# tm7_revF.net
KiCad netlist of a schematic drawn in EAGLE
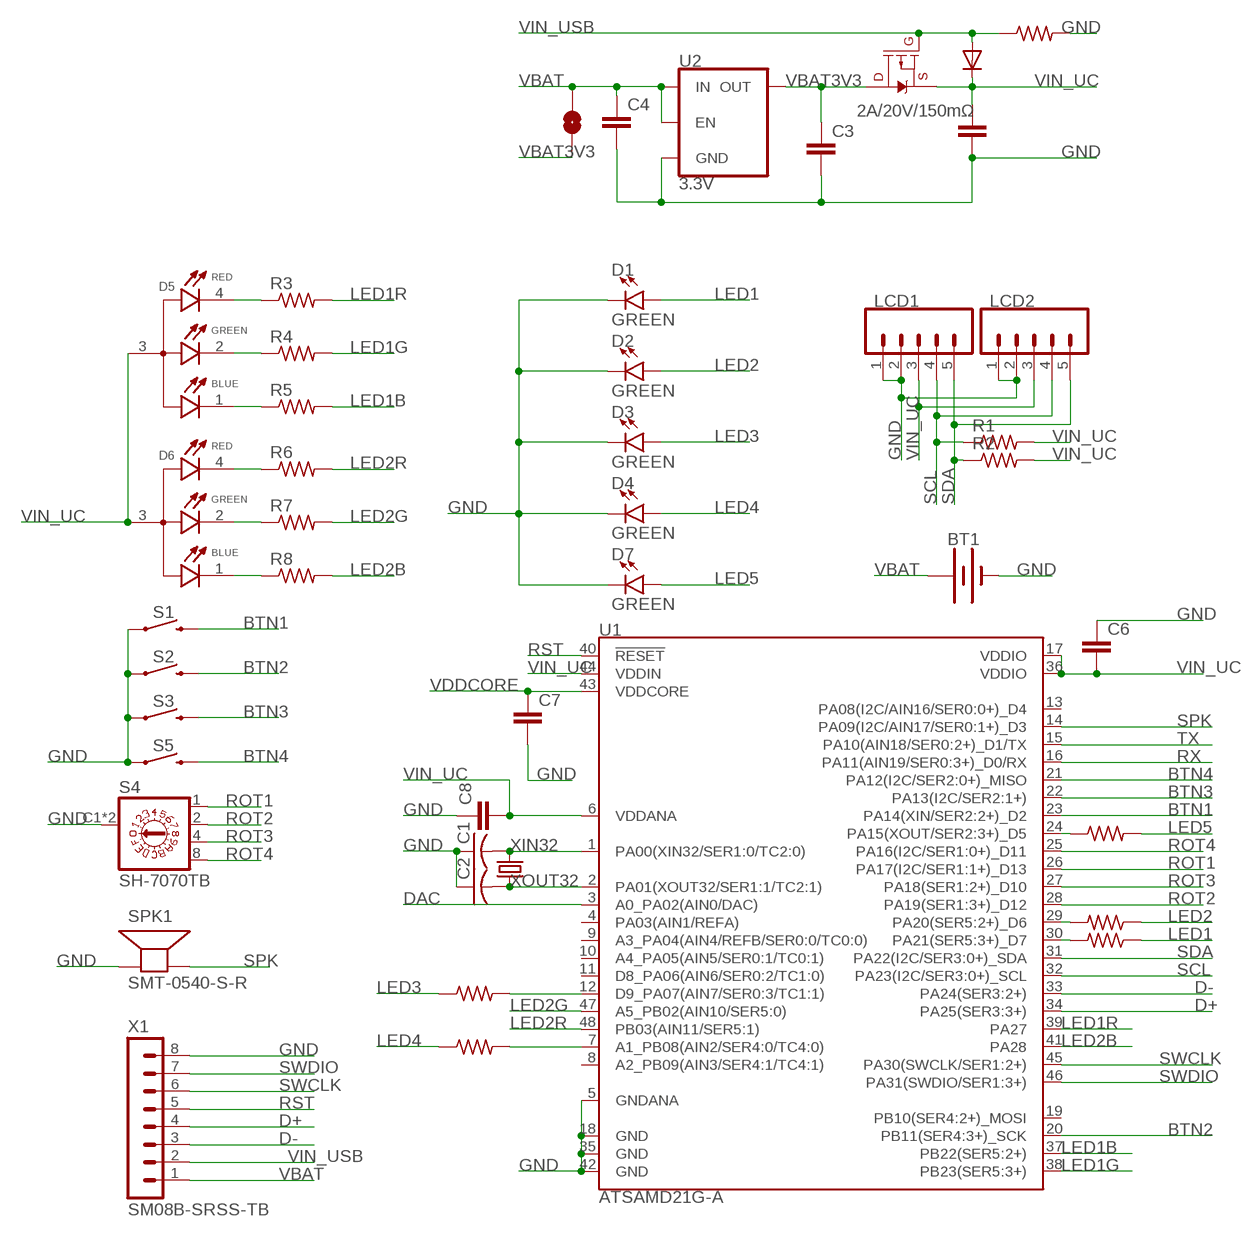
[diagram p0: schematic, sheet 1]

(export (version "E")
  (design (tool "Eeschema 10.0.6"))
  (components
    (comp (ref "BT1")
      (value "BATTERY-20MM_SMD_4LEGS_OVERPASTE_INNER")
      (footprint "eagle-import:BATTCON_20MM_4LEGS_OVERPASTE_INNER")
      (libsource (lib "eagle-import") (part "BATTERY-20MM_SMD_4LEGS_OVERPASTE_INNER"))
    )
    (comp (ref "C1")
      (value "C-USC0603")
      (footprint "eagle-import:C0603")
      (libsource (lib "eagle-import") (part "C-USC0603"))
    )
    (comp (ref "C2")
      (value "C-USC0603")
      (footprint "eagle-import:C0603")
      (libsource (lib "eagle-import") (part "C-USC0603"))
    )
    (comp (ref "C3")
      (value "C-EUC0603")
      (footprint "eagle-import:C0603")
      (libsource (lib "eagle-import") (part "C-EUC0603"))
    )
    (comp (ref "C4")
      (value "C-EUC0603")
      (footprint "eagle-import:C0603")
      (libsource (lib "eagle-import") (part "C-EUC0603"))
    )
    (comp (ref "C6")
      (value "C-EUC0603")
      (footprint "eagle-import:C0603")
      (libsource (lib "eagle-import") (part "C-EUC0603"))
    )
    (comp (ref "C7")
      (value "C-EUC0603")
      (footprint "eagle-import:C0603")
      (libsource (lib "eagle-import") (part "C-EUC0603"))
    )
    (comp (ref "C8")
      (value "C-EUC0603")
      (footprint "eagle-import:C0603")
      (libsource (lib "eagle-import") (part "C-EUC0603"))
    )
    (comp (ref "C9")
      (value "C-EUC0603")
      (footprint "eagle-import:C0603")
      (libsource (lib "eagle-import") (part "C-EUC0603"))
    )
    (comp (ref "D1")
      (value "GREEN")
      (footprint "eagle-import:LED-1206")
      (libsource (lib "eagle-import") (part "LED-GREEN1206"))
    )
    (comp (ref "D2")
      (value "GREEN")
      (footprint "eagle-import:LED-1206")
      (libsource (lib "eagle-import") (part "LED-GREEN1206"))
    )
    (comp (ref "D3")
      (value "GREEN")
      (footprint "eagle-import:LED-1206")
      (libsource (lib "eagle-import") (part "LED-GREEN1206"))
    )
    (comp (ref "D4")
      (value "GREEN")
      (footprint "eagle-import:LED-1206")
      (libsource (lib "eagle-import") (part "LED-GREEN1206"))
    )
    (comp (ref "D5")
      (value "EAST1616RGBA3")
      (footprint "eagle-import:LED_EAST1616RGBA3")
      (fields (field (name "MF") "Everlight Electronics"))
      (libsource (lib "eagle-import") (part "EAST1616RGBA3"))
    )
    (comp (ref "D6")
      (value "EAST1616RGBA3")
      (footprint "eagle-import:LED_EAST1616RGBA3")
      (fields (field (name "MF") "Everlight Electronics"))
      (libsource (lib "eagle-import") (part "EAST1616RGBA3"))
    )
    (comp (ref "D7")
      (value "GREEN")
      (footprint "eagle-import:LED-1206")
      (libsource (lib "eagle-import") (part "LED-GREEN1206"))
    )
    (comp (ref "D8")
      (value "DIODESOD-323F")
      (footprint "eagle-import:SOD-323F")
      (libsource (lib "eagle-import") (part "DIODESOD-323F"))
    )
    (comp (ref "JP1")
      (value "JUMPER-SMT_2_NO_NO-SILK")
      (footprint "eagle-import:SMT-JUMPER_2_NO_NO-SILK")
      (libsource (lib "eagle-import") (part "JUMPER-SMT_2_NO_NO-SILK"))
    )
    (comp (ref "LCD1")
      (value "CONN_05VERT_FEMALE_HEADER")
      (footprint "eagle-import:1X05_SMD_VERTICAL_COMBO")
      (libsource (lib "eagle-import") (part "CONN_05VERT_FEMALE_HEADER"))
    )
    (comp (ref "LCD2")
      (value "CONN_05VERT_FEMALE_HEADER")
      (footprint "eagle-import:1X05_SMD_VERTICAL_COMBO")
      (libsource (lib "eagle-import") (part "CONN_05VERT_FEMALE_HEADER"))
    )
    (comp (ref "Q1")
      (value "2A/20V/150mΩ")
      (footprint "eagle-import:SOT26")
      (libsource (lib "eagle-import") (part "MOSFET_PCH_DUAL-DMP2240UDM"))
    )
    (comp (ref "R1")
      (value "R-US_R0603")
      (footprint "eagle-import:R0603")
      (libsource (lib "eagle-import") (part "rcl_334_R-US_R0603"))
    )
    (comp (ref "R2")
      (value "R-US_R0603")
      (footprint "eagle-import:R0603")
      (libsource (lib "eagle-import") (part "rcl_334_R-US_R0603"))
    )
    (comp (ref "R3")
      (value "R-US_R0603")
      (footprint "eagle-import:R0603")
      (libsource (lib "eagle-import") (part "rcl_334_R-US_R0603"))
    )
    (comp (ref "R4")
      (value "R-US_R0603")
      (footprint "eagle-import:R0603")
      (libsource (lib "eagle-import") (part "rcl_334_R-US_R0603"))
    )
    (comp (ref "R5")
      (value "R-US_R0603")
      (footprint "eagle-import:R0603")
      (libsource (lib "eagle-import") (part "rcl_334_R-US_R0603"))
    )
    (comp (ref "R6")
      (value "R-US_R0603")
      (footprint "eagle-import:R0603")
      (libsource (lib "eagle-import") (part "rcl_334_R-US_R0603"))
    )
    (comp (ref "R7")
      (value "R-US_R0603")
      (footprint "eagle-import:R0603")
      (libsource (lib "eagle-import") (part "rcl_334_R-US_R0603"))
    )
    (comp (ref "R8")
      (value "R-US_R0603")
      (footprint "eagle-import:R0603")
      (libsource (lib "eagle-import") (part "rcl_334_R-US_R0603"))
    )
    (comp (ref "R9")
      (value "R-US_R0603")
      (footprint "eagle-import:R0603")
      (libsource (lib "eagle-import") (part "rcl_334_R-US_R0603"))
    )
    (comp (ref "R10")
      (value "R-US_R0603")
      (footprint "eagle-import:R0603")
      (libsource (lib "eagle-import") (part "rcl_334_R-US_R0603"))
    )
    (comp (ref "R11")
      (value "R-US_R0603")
      (footprint "eagle-import:R0603")
      (libsource (lib "eagle-import") (part "rcl_334_R-US_R0603"))
    )
    (comp (ref "R12")
      (value "R-US_R0603")
      (footprint "eagle-import:R0603")
      (libsource (lib "eagle-import") (part "rcl_334_R-US_R0603"))
    )
    (comp (ref "R13")
      (value "R-US_R0603")
      (footprint "eagle-import:R0603")
      (libsource (lib "eagle-import") (part "rcl_334_R-US_R0603"))
    )
    (comp (ref "R14")
      (value "R-US_R0603")
      (footprint "eagle-import:R0603")
      (libsource (lib "eagle-import") (part "R-US_R0603"))
    )
    (comp (ref "S1")
      (value "MOMENTARY-SWITCH-SPST-SMD-6.0X3.5MM")
      (footprint "eagle-import:TACTILE_SWITCH_SMD_6.0X3.5MM")
      (libsource (lib "eagle-import") (part "MOMENTARY-SWITCH-SPST-SMD-6.0X3.5MM"))
    )
    (comp (ref "S2")
      (value "MOMENTARY-SWITCH-SPST-SMD-6.0X3.5MM")
      (footprint "eagle-import:TACTILE_SWITCH_SMD_6.0X3.5MM")
      (libsource (lib "eagle-import") (part "MOMENTARY-SWITCH-SPST-SMD-6.0X3.5MM"))
    )
    (comp (ref "S3")
      (value "MOMENTARY-SWITCH-SPST-SMD-6.0X3.5MM")
      (footprint "eagle-import:TACTILE_SWITCH_SMD_6.0X3.5MM")
      (libsource (lib "eagle-import") (part "MOMENTARY-SWITCH-SPST-SMD-6.0X3.5MM"))
    )
    (comp (ref "S4")
      (value "SH-7070TB")
      (footprint "eagle-import:SH-7070B")
      (fields (field (name "MF") "Nidec Copal"))
      (libsource (lib "eagle-import") (part "SH-7070TB"))
    )
    (comp (ref "S5")
      (value "MOMENTARY-SWITCH-SPST-SMD-6.0X3.5MM")
      (footprint "eagle-import:TACTILE_SWITCH_SMD_6.0X3.5MM")
      (libsource (lib "eagle-import") (part "MOMENTARY-SWITCH-SPST-SMD-6.0X3.5MM"))
    )
    (comp (ref "SPK1")
      (value "SMT-0540-S-R")
      (footprint "eagle-import:SMT-0540-S-R")
      (fields (field (name "MF") "PUI"))
      (libsource (lib "eagle-import") (part "SMT-0540-S-R"))
    )
    (comp (ref "U1")
      (value "ATSAMD21G-A")
      (footprint "eagle-import:TQFP-48")
      (libsource (lib "eagle-import") (part "ATSAMD21G-A"))
    )
    (comp (ref "U2")
      (value "3.3V")
      (footprint "eagle-import:SOT23-5")
      (libsource (lib "eagle-import") (part "V_REG_AP2112K-3.3V"))
    )
    (comp (ref "X1")
      (value "SM08B-SRSS-TB")
      (footprint "eagle-import:SM08B-SRSS-TB")
      (libsource (lib "eagle-import") (part "SM08B-SRSS-TB"))
    )
    (comp (ref "Y1")
      (value "32.768kHz")
      (footprint "eagle-import:CRYSTAL-SMD-3.2X1.5MM")
      (libsource (lib "eagle-import") (part "CRYSTAL-32.768KHZSMD-3.2X1.5"))
    )
  )
  (nets
    (net (code "1") (name "/BTN1") (class "Default")
      (node (ref "S1") (pin "2") (pinfunction "2_2") (pintype "passive"))
      (node (ref "U1") (pin "23") (pinfunction "PA14(XIN/SER2:2+)_D2_23") (pintype "bidirectional"))
    )
    (net (code "2") (name "/BTN2") (class "Default")
      (node (ref "S2") (pin "2") (pinfunction "2_2") (pintype "passive"))
      (node (ref "U1") (pin "20") (pinfunction "PB11(SER4:3+)_SCK_20") (pintype "bidirectional"))
    )
    (net (code "3") (name "/BTN3") (class "Default")
      (node (ref "S3") (pin "2") (pinfunction "2_2") (pintype "passive"))
      (node (ref "U1") (pin "22") (pinfunction "PA13(I2C/SER2:1+)_22") (pintype "bidirectional"))
    )
    (net (code "4") (name "/BTN4") (class "Default")
      (node (ref "S5") (pin "2") (pinfunction "2_2") (pintype "passive"))
      (node (ref "U1") (pin "21") (pinfunction "PA12(I2C/SER2:0+)_MISO_21") (pintype "bidirectional"))
    )
    (net (code "5") (name "/D+") (class "Default")
      (node (ref "U1") (pin "34") (pinfunction "PA25(SER3:3+)_34") (pintype "bidirectional"))
      (node (ref "X1") (pin "4") (pinfunction "4_4") (pintype "passive"))
    )
    (net (code "6") (name "/D-") (class "Default")
      (node (ref "U1") (pin "33") (pinfunction "PA24(SER3:2+)_33") (pintype "bidirectional"))
      (node (ref "X1") (pin "3") (pinfunction "3_3") (pintype "passive"))
    )
    (net (code "7") (name "/DAC") (class "Default")
      (node (ref "U1") (pin "3") (pinfunction "A0_PA02(AIN0/DAC)_3") (pintype "bidirectional"))
    )
    (net (code "8") (name "/GND") (class "Default")
      (node (ref "BT1") (pin "2") (pinfunction "-_2") (pintype "power_in"))
      (node (ref "C1") (pin "1") (pinfunction "1_1") (pintype "passive"))
      (node (ref "C2") (pin "1") (pinfunction "1_1") (pintype "passive"))
      (node (ref "C3") (pin "2") (pinfunction "2_2") (pintype "passive"))
      (node (ref "C4") (pin "2") (pinfunction "2_2") (pintype "passive"))
      (node (ref "C6") (pin "1") (pinfunction "1_1") (pintype "passive"))
      (node (ref "C7") (pin "2") (pinfunction "2_2") (pintype "passive"))
      (node (ref "C8") (pin "1") (pinfunction "1_1") (pintype "passive"))
      (node (ref "C9") (pin "2") (pinfunction "2_2") (pintype "passive"))
      (node (ref "D1") (pin "C") (pinfunction "C_C") (pintype "passive"))
      (node (ref "D2") (pin "C") (pinfunction "C_C") (pintype "passive"))
      (node (ref "D3") (pin "C") (pinfunction "C_C") (pintype "passive"))
      (node (ref "D4") (pin "C") (pinfunction "C_C") (pintype "passive"))
      (node (ref "D7") (pin "C") (pinfunction "C_C") (pintype "passive"))
      (node (ref "LCD1") (pin "1") (pinfunction "1_1") (pintype "passive"))
      (node (ref "LCD1") (pin "2") (pinfunction "2_2") (pintype "passive"))
      (node (ref "LCD2") (pin "1") (pinfunction "1_1") (pintype "passive"))
      (node (ref "LCD2") (pin "2") (pinfunction "2_2") (pintype "passive"))
      (node (ref "R14") (pin "2") (pinfunction "2_2") (pintype "passive"))
      (node (ref "S1") (pin "1") (pinfunction "1_1") (pintype "passive"))
      (node (ref "S2") (pin "1") (pinfunction "1_1") (pintype "passive"))
      (node (ref "S3") (pin "1") (pinfunction "1_1") (pintype "passive"))
      (node (ref "S4") (pin "C1") (pinfunction "C_C1") (pintype "passive"))
      (node (ref "S4") (pin "C2") (pinfunction "C_C2") (pintype "passive"))
      (node (ref "S5") (pin "1") (pinfunction "1_1") (pintype "passive"))
      (node (ref "SPK1") (pin "-") (pinfunction "+_-") (pintype "passive"))
      (node (ref "U1") (pin "18") (pinfunction "GND_18") (pintype "bidirectional"))
      (node (ref "U1") (pin "35") (pinfunction "GND_35") (pintype "bidirectional"))
      (node (ref "U1") (pin "42") (pinfunction "GND_42") (pintype "bidirectional"))
      (node (ref "U1") (pin "5") (pinfunction "GNDANA_5") (pintype "bidirectional"))
      (node (ref "U2") (pin "2") (pinfunction "GND_2") (pintype "input"))
      (node (ref "X1") (pin "8") (pinfunction "8_8") (pintype "passive"))
    )
    (net (code "9") (name "/LED1") (class "Default")
      (node (ref "D1") (pin "A") (pinfunction "A_A") (pintype "passive"))
      (node (ref "R9") (pin "1") (pinfunction "1_1") (pintype "passive"))
    )
    (net (code "10") (name "/LED1B") (class "Default")
      (node (ref "R5") (pin "2") (pinfunction "2_2") (pintype "passive"))
      (node (ref "U1") (pin "37") (pinfunction "PB22(SER5:2+)_37") (pintype "bidirectional"))
    )
    (net (code "11") (name "/LED1G") (class "Default")
      (node (ref "R4") (pin "2") (pinfunction "2_2") (pintype "passive"))
      (node (ref "U1") (pin "38") (pinfunction "PB23(SER5:3+)_38") (pintype "bidirectional"))
    )
    (net (code "12") (name "/LED1R") (class "Default")
      (node (ref "R3") (pin "2") (pinfunction "2_2") (pintype "passive"))
      (node (ref "U1") (pin "39") (pinfunction "PA27_39") (pintype "bidirectional"))
    )
    (net (code "13") (name "/LED2") (class "Default")
      (node (ref "D2") (pin "A") (pinfunction "A_A") (pintype "passive"))
      (node (ref "R10") (pin "1") (pinfunction "1_1") (pintype "passive"))
    )
    (net (code "14") (name "/LED2B") (class "Default")
      (node (ref "R8") (pin "2") (pinfunction "2_2") (pintype "passive"))
      (node (ref "U1") (pin "41") (pinfunction "PA28_41") (pintype "bidirectional"))
    )
    (net (code "15") (name "/LED2G") (class "Default")
      (node (ref "R7") (pin "2") (pinfunction "2_2") (pintype "passive"))
      (node (ref "U1") (pin "47") (pinfunction "A5_PB02(AIN10/SER5:0)_47") (pintype "bidirectional"))
    )
    (net (code "16") (name "/LED2R") (class "Default")
      (node (ref "R6") (pin "2") (pinfunction "2_2") (pintype "passive"))
      (node (ref "U1") (pin "48") (pinfunction "PB03(AIN11/SER5:1)_48") (pintype "bidirectional"))
    )
    (net (code "17") (name "/LED3") (class "Default")
      (node (ref "D3") (pin "A") (pinfunction "A_A") (pintype "passive"))
      (node (ref "R11") (pin "1") (pinfunction "1_1") (pintype "passive"))
    )
    (net (code "18") (name "/LED4") (class "Default")
      (node (ref "D4") (pin "A") (pinfunction "A_A") (pintype "passive"))
      (node (ref "R12") (pin "1") (pinfunction "1_1") (pintype "passive"))
    )
    (net (code "19") (name "/LED5") (class "Default")
      (node (ref "D7") (pin "A") (pinfunction "A_A") (pintype "passive"))
      (node (ref "R13") (pin "2") (pinfunction "2_2") (pintype "passive"))
    )
    (net (code "20") (name "/ROT1") (class "Default")
      (node (ref "S4") (pin "1") (pinfunction "1_1") (pintype "passive"))
      (node (ref "U1") (pin "26") (pinfunction "PA17(I2C/SER1:1+)_D13_26") (pintype "bidirectional"))
    )
    (net (code "21") (name "/ROT2") (class "Default")
      (node (ref "S4") (pin "2") (pinfunction "2_2") (pintype "passive"))
      (node (ref "U1") (pin "28") (pinfunction "PA19(SER1:3+)_D12_28") (pintype "bidirectional"))
    )
    (net (code "22") (name "/ROT3") (class "Default")
      (node (ref "S4") (pin "4") (pinfunction "4_4") (pintype "passive"))
      (node (ref "U1") (pin "27") (pinfunction "PA18(SER1:2+)_D10_27") (pintype "bidirectional"))
    )
    (net (code "23") (name "/ROT4") (class "Default")
      (node (ref "S4") (pin "8") (pinfunction "8_8") (pintype "passive"))
      (node (ref "U1") (pin "25") (pinfunction "PA16(I2C/SER1:0+)_D11_25") (pintype "bidirectional"))
    )
    (net (code "24") (name "/RST") (class "Default")
      (node (ref "U1") (pin "40") (pinfunction "~{RESET}_40") (pintype "bidirectional"))
      (node (ref "X1") (pin "5") (pinfunction "5_5") (pintype "passive"))
    )
    (net (code "25") (name "/RX") (class "Default")
      (node (ref "U1") (pin "16") (pinfunction "PA11(AIN19/SER0:3+)_D0/RX_16") (pintype "bidirectional"))
    )
    (net (code "26") (name "/SCL") (class "Default")
      (node (ref "LCD1") (pin "4") (pinfunction "4_4") (pintype "passive"))
      (node (ref "LCD2") (pin "4") (pinfunction "4_4") (pintype "passive"))
      (node (ref "R1") (pin "1") (pinfunction "1_1") (pintype "passive"))
      (node (ref "U1") (pin "32") (pinfunction "PA23(I2C/SER3:0+)_SCL_32") (pintype "bidirectional"))
    )
    (net (code "27") (name "/SDA") (class "Default")
      (node (ref "LCD1") (pin "5") (pinfunction "5_5") (pintype "passive"))
      (node (ref "LCD2") (pin "5") (pinfunction "5_5") (pintype "passive"))
      (node (ref "R2") (pin "1") (pinfunction "1_1") (pintype "passive"))
      (node (ref "U1") (pin "31") (pinfunction "PA22(I2C/SER3:0+)_SDA_31") (pintype "bidirectional"))
    )
    (net (code "28") (name "/SPK") (class "Default")
      (node (ref "SPK1") (pin "+") (pinfunction "-_+") (pintype "passive"))
      (node (ref "U1") (pin "14") (pinfunction "PA09(I2C/AIN17/SER0:1+)_D3_14") (pintype "bidirectional"))
    )
    (net (code "29") (name "/SWCLK") (class "Default")
      (node (ref "U1") (pin "45") (pinfunction "PA30(SWCLK/SER1:2+)_45") (pintype "bidirectional"))
      (node (ref "X1") (pin "6") (pinfunction "6_6") (pintype "passive"))
    )
    (net (code "30") (name "/SWDIO") (class "Default")
      (node (ref "U1") (pin "46") (pinfunction "PA31(SWDIO/SER1:3+)_46") (pintype "bidirectional"))
      (node (ref "X1") (pin "7") (pinfunction "7_7") (pintype "passive"))
    )
    (net (code "31") (name "/TX") (class "Default")
      (node (ref "U1") (pin "15") (pinfunction "PA10(AIN18/SER0:2+)_D1/TX_15") (pintype "bidirectional"))
    )
    (net (code "32") (name "/VBAT") (class "Default")
      (node (ref "BT1") (pin "1") (pinfunction "+_1") (pintype "power_in"))
      (node (ref "C4") (pin "1") (pinfunction "1_1") (pintype "passive"))
      (node (ref "JP1") (pin "2") (pinfunction "2_2") (pintype "passive"))
      (node (ref "U2") (pin "1") (pinfunction "IN_1") (pintype "input"))
      (node (ref "U2") (pin "3") (pinfunction "EN_3") (pintype "input"))
      (node (ref "X1") (pin "1") (pinfunction "1_1") (pintype "passive"))
    )
    (net (code "33") (name "/VBAT3V3") (class "Default")
      (node (ref "C3") (pin "1") (pinfunction "1_1") (pintype "passive"))
      (node (ref "JP1") (pin "1") (pinfunction "1_1") (pintype "passive"))
      (node (ref "Q1") (pin "D1") (pinfunction "D_D1") (pintype "bidirectional"))
      (node (ref "U2") (pin "5") (pinfunction "OUT_5") (pintype "passive"))
    )
    (net (code "34") (name "/VDDCORE") (class "Default")
      (node (ref "C7") (pin "1") (pinfunction "1_1") (pintype "passive"))
      (node (ref "U1") (pin "43") (pinfunction "VDDCORE_43") (pintype "bidirectional"))
    )
    (net (code "35") (name "/VIN_UC") (class "Default")
      (node (ref "C6") (pin "2") (pinfunction "2_2") (pintype "passive"))
      (node (ref "C8") (pin "2") (pinfunction "2_2") (pintype "passive"))
      (node (ref "C9") (pin "1") (pinfunction "1_1") (pintype "passive"))
      (node (ref "D5") (pin "3") (pinfunction "A_3") (pintype "passive"))
      (node (ref "D6") (pin "3") (pinfunction "A_3") (pintype "passive"))
      (node (ref "D8") (pin "C") (pinfunction "C_C") (pintype "passive"))
      (node (ref "LCD1") (pin "3") (pinfunction "3_3") (pintype "passive"))
      (node (ref "LCD2") (pin "3") (pinfunction "3_3") (pintype "passive"))
      (node (ref "Q1") (pin "S1") (pinfunction "S_S1") (pintype "bidirectional"))
      (node (ref "R1") (pin "2") (pinfunction "2_2") (pintype "passive"))
      (node (ref "R2") (pin "2") (pinfunction "2_2") (pintype "passive"))
      (node (ref "U1") (pin "17") (pinfunction "VDDIO_17") (pintype "bidirectional"))
      (node (ref "U1") (pin "36") (pinfunction "VDDIO_36") (pintype "bidirectional"))
      (node (ref "U1") (pin "44") (pinfunction "VDDIN_44") (pintype "bidirectional"))
      (node (ref "U1") (pin "6") (pinfunction "VDDANA_6") (pintype "bidirectional"))
    )
    (net (code "36") (name "/VIN_USB") (class "Default")
      (node (ref "D8") (pin "A") (pinfunction "A_A") (pintype "passive"))
      (node (ref "Q1") (pin "G1") (pinfunction "G_G1") (pintype "bidirectional"))
      (node (ref "R14") (pin "1") (pinfunction "1_1") (pintype "passive"))
      (node (ref "X1") (pin "2") (pinfunction "2_2") (pintype "passive"))
    )
    (net (code "37") (name "/XIN32") (class "Default")
      (node (ref "C1") (pin "2") (pinfunction "2_2") (pintype "passive"))
      (node (ref "U1") (pin "1") (pinfunction "PA00(XIN32/SER1:0/TC2:0)_1") (pintype "bidirectional"))
      (node (ref "Y1") (pin "P$2") (pinfunction "2_P$2") (pintype "passive"))
    )
    (net (code "38") (name "/XOUT32") (class "Default")
      (node (ref "C2") (pin "2") (pinfunction "2_2") (pintype "passive"))
      (node (ref "U1") (pin "2") (pinfunction "PA01(XOUT32/SER1:1/TC2:1)_2") (pintype "bidirectional"))
      (node (ref "Y1") (pin "P$1") (pinfunction "1_P$1") (pintype "passive"))
    )
    (net (code "39") (name "Net-(D5-B_C)") (class "Default")
      (node (ref "D5") (pin "1") (pinfunction "B_C_1") (pintype "passive"))
      (node (ref "R5") (pin "1") (pinfunction "1_1") (pintype "passive"))
    )
    (net (code "40") (name "Net-(D5-G_C)") (class "Default")
      (node (ref "D5") (pin "2") (pinfunction "G_C_2") (pintype "passive"))
      (node (ref "R4") (pin "1") (pinfunction "1_1") (pintype "passive"))
    )
    (net (code "41") (name "Net-(D5-R_C)") (class "Default")
      (node (ref "D5") (pin "4") (pinfunction "R_C_4") (pintype "passive"))
      (node (ref "R3") (pin "1") (pinfunction "1_1") (pintype "passive"))
    )
    (net (code "42") (name "Net-(D6-B_C)") (class "Default")
      (node (ref "D6") (pin "1") (pinfunction "B_C_1") (pintype "passive"))
      (node (ref "R8") (pin "1") (pinfunction "1_1") (pintype "passive"))
    )
    (net (code "43") (name "Net-(D6-G_C)") (class "Default")
      (node (ref "D6") (pin "2") (pinfunction "G_C_2") (pintype "passive"))
      (node (ref "R7") (pin "1") (pinfunction "1_1") (pintype "passive"))
    )
    (net (code "44") (name "Net-(D6-R_C)") (class "Default")
      (node (ref "D6") (pin "4") (pinfunction "R_C_4") (pintype "passive"))
      (node (ref "R6") (pin "1") (pinfunction "1_1") (pintype "passive"))
    )
    (net (code "45") (name "Net-(U1-A1_PB08(AIN2{slash}SER4:0{slash}TC4:0))") (class "Default")
      (node (ref "R12") (pin "2") (pinfunction "2_2") (pintype "passive"))
      (node (ref "U1") (pin "7") (pinfunction "A1_PB08(AIN2/SER4:0/TC4:0)_7") (pintype "bidirectional"))
    )
    (net (code "46") (name "Net-(U1-D9_PA07(AIN7{slash}SER0:3{slash}TC1:1))") (class "Default")
      (node (ref "R11") (pin "2") (pinfunction "2_2") (pintype "passive"))
      (node (ref "U1") (pin "12") (pinfunction "D9_PA07(AIN7/SER0:3/TC1:1)_12") (pintype "bidirectional"))
    )
    (net (code "47") (name "Net-(U1-PA15(XOUT{slash}SER2:3+)_D5)") (class "Default")
      (node (ref "R13") (pin "1") (pinfunction "1_1") (pintype "passive"))
      (node (ref "U1") (pin "24") (pinfunction "PA15(XOUT/SER2:3+)_D5_24") (pintype "bidirectional"))
    )
    (net (code "48") (name "Net-(U1-PA20(SER5:2+)_D6)") (class "Default")
      (node (ref "R10") (pin "2") (pinfunction "2_2") (pintype "passive"))
      (node (ref "U1") (pin "29") (pinfunction "PA20(SER5:2+)_D6_29") (pintype "bidirectional"))
    )
    (net (code "49") (name "Net-(U1-PA21(SER5:3+)_D7)") (class "Default")
      (node (ref "R9") (pin "2") (pinfunction "2_2") (pintype "passive"))
      (node (ref "U1") (pin "30") (pinfunction "PA21(SER5:3+)_D7_30") (pintype "bidirectional"))
    )
    (net (code "50") (name "unconnected-(U1-A2_PB09(AIN3{slash}SER4:1{slash}TC4:1)-Pad8)") (class "Default")
      (node (ref "U1") (pin "8") (pinfunction "A2_PB09(AIN3/SER4:1/TC4:1)_8") (pintype "bidirectional"))
    )
    (net (code "51") (name "unconnected-(U1-A3_PA04(AIN4{slash}REFB{slash}SER0:0{slash}TC0:0)-Pad9)") (class "Default")
      (node (ref "U1") (pin "9") (pinfunction "A3_PA04(AIN4/REFB/SER0:0/TC0:0)_9") (pintype "bidirectional"))
    )
    (net (code "52") (name "unconnected-(U1-A4_PA05(AIN5{slash}SER0:1{slash}TC0:1)-Pad10)") (class "Default")
      (node (ref "U1") (pin "10") (pinfunction "A4_PA05(AIN5/SER0:1/TC0:1)_10") (pintype "bidirectional"))
    )
    (net (code "53") (name "unconnected-(U1-D8_PA06(AIN6{slash}SER0:2{slash}TC1:0)-Pad11)") (class "Default")
      (node (ref "U1") (pin "11") (pinfunction "D8_PA06(AIN6/SER0:2/TC1:0)_11") (pintype "bidirectional"))
    )
    (net (code "54") (name "unconnected-(U1-PA03(AIN1{slash}REFA)-Pad4)") (class "Default")
      (node (ref "U1") (pin "4") (pinfunction "PA03(AIN1/REFA)_4") (pintype "bidirectional"))
    )
    (net (code "55") (name "unconnected-(U1-PA08(I2C{slash}AIN16{slash}SER0:0+)_D4-Pad13)") (class "Default")
      (node (ref "U1") (pin "13") (pinfunction "PA08(I2C/AIN16/SER0:0+)_D4_13") (pintype "bidirectional"))
    )
    (net (code "56") (name "unconnected-(U1-PB10(SER4:2+)_MOSI-Pad19)") (class "Default")
      (node (ref "U1") (pin "19") (pinfunction "PB10(SER4:2+)_MOSI_19") (pintype "bidirectional"))
    )
  )
)
